# TinyFunctionGenerator.net
KiCad netlist of a schematic drawn in EAGLE
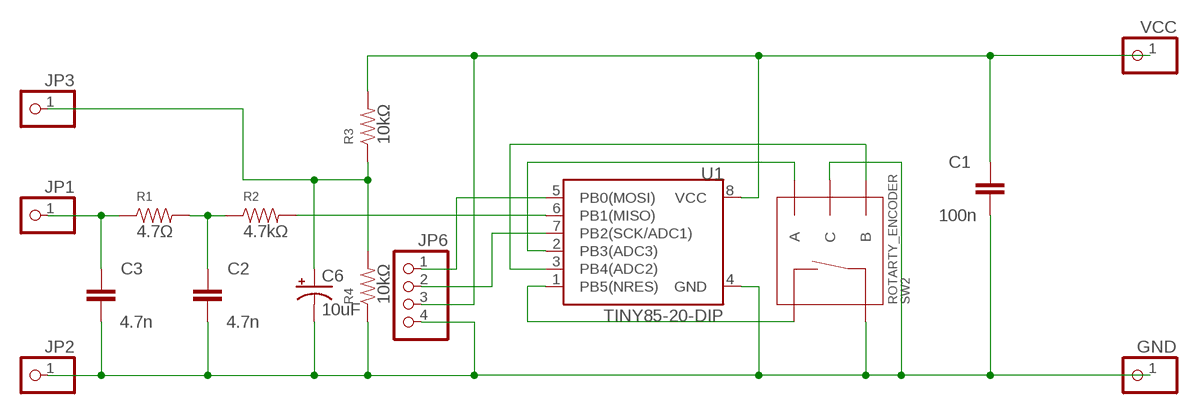
[diagram p0: schematic, sheet 1]

(export (version "E")
  (design (tool "Eeschema 10.0.6"))
  (components
    (comp (ref "C1")
      (value "100n")
      (footprint "eagle-import:AXIAL-5MM")
      (libsource (lib "eagle-import") (part "CAP_"))
    )
    (comp (ref "C2")
      (value "4.7n")
      (footprint "eagle-import:CAP-PTH-SMALL")
      (libsource (lib "eagle-import") (part "CAPPTH"))
    )
    (comp (ref "C3")
      (value "4.7n")
      (footprint "eagle-import:CAP-PTH-SMALL")
      (libsource (lib "eagle-import") (part "CAPPTH"))
    )
    (comp (ref "C6")
      (value "10uF")
      (footprint "eagle-import:CPOL-RADIAL-10UF-25V")
      (libsource (lib "eagle-import") (part "10UF-25V-20%(PTH)"))
    )
    (comp (ref "GND")
      (value "PINHD-1X1CB")
      (footprint "eagle-import:1X01-CLEANBIG")
      (libsource (lib "eagle-import") (part "PINHD-1X1CB"))
    )
    (comp (ref "JP1")
      (value "PINHD-1X1CB")
      (footprint "eagle-import:1X01-CLEANBIG")
      (libsource (lib "eagle-import") (part "PINHD-1X1CB"))
    )
    (comp (ref "JP2")
      (value "PINHD-1X1CB")
      (footprint "eagle-import:1X01-CLEANBIG")
      (libsource (lib "eagle-import") (part "PINHD-1X1CB"))
    )
    (comp (ref "JP3")
      (value "PINHD-1X1CB")
      (footprint "eagle-import:1X01-CLEANBIG")
      (libsource (lib "eagle-import") (part "PINHD-1X1CB"))
    )
    (comp (ref "JP6")
      (value "HEADER-1X4ROUND")
      (footprint "eagle-import:1X04_ROUND")
      (libsource (lib "eagle-import") (part "HEADER-1X4ROUND"))
    )
    (comp (ref "R1")
      (value "4.7Ω")
      (footprint "eagle-import:AXIAL-0.4")
      (libsource (lib "eagle-import") (part "RESISTORPTH-1/4W"))
    )
    (comp (ref "R2")
      (value "4.7kΩ")
      (footprint "eagle-import:AXIAL-0.4")
      (libsource (lib "eagle-import") (part "RESISTORPTH-1/4W"))
    )
    (comp (ref "R3")
      (value "10kΩ")
      (footprint "eagle-import:AXIAL-0.4")
      (libsource (lib "eagle-import") (part "RESISTORPTH-1/4W"))
    )
    (comp (ref "R4")
      (value "10kΩ")
      (footprint "eagle-import:AXIAL-0.4")
      (libsource (lib "eagle-import") (part "RESISTORPTH-1/4W"))
    )
    (comp (ref "SW2")
      (value "ROTARTY_ENCODER")
      (footprint "eagle-import:ROTARY_ENC_PLAIN")
      (libsource (lib "eagle-import") (part "ROTARTY_ENCODER"))
    )
    (comp (ref "U1")
      (value "TINY85-20-DIP")
      (footprint "eagle-import:DIP08")
      (libsource (lib "eagle-import") (part "ATTINY45TINY85-20-DIP"))
    )
    (comp (ref "VCC")
      (value "PINHD-1X1CB")
      (footprint "eagle-import:1X01-CLEANBIG")
      (libsource (lib "eagle-import") (part "PINHD-1X1CB"))
    )
  )
  (nets
    (net (code "1") (name "Net-(C1-1)") (class "Default")
      (node (ref "C1") (pin "P$1") (pinfunction "1_P$1") (pintype "passive"))
      (node (ref "JP6") (pin "3") (pinfunction "3_3") (pintype "passive"))
      (node (ref "R3") (pin "P$2") (pinfunction "2_P$2") (pintype "passive"))
      (node (ref "U1") (pin "8") (pinfunction "VCC_8") (pintype "bidirectional"))
      (node (ref "VCC") (pin "1") (pinfunction "1_1") (pintype "passive"))
    )
    (net (code "2") (name "Net-(C1-2)") (class "Default")
      (node (ref "C1") (pin "P$2") (pinfunction "2_P$2") (pintype "passive"))
      (node (ref "C2") (pin "2") (pinfunction "2_2") (pintype "passive"))
      (node (ref "C3") (pin "2") (pinfunction "2_2") (pintype "passive"))
      (node (ref "C6") (pin "2") (pinfunction "-_2") (pintype "passive"))
      (node (ref "GND") (pin "1") (pinfunction "1_1") (pintype "passive"))
      (node (ref "JP2") (pin "1") (pinfunction "1_1") (pintype "passive"))
      (node (ref "JP6") (pin "4") (pinfunction "4_4") (pintype "passive"))
      (node (ref "R4") (pin "P$1") (pinfunction "1_P$1") (pintype "passive"))
      (node (ref "SW2") (pin "C") (pinfunction "C_C") (pintype "bidirectional"))
      (node (ref "SW2") (pin "SW+") (pinfunction "SW+_SW+") (pintype "bidirectional"))
      (node (ref "U1") (pin "4") (pinfunction "GND_4") (pintype "bidirectional"))
    )
    (net (code "3") (name "Net-(C6-+)") (class "Default")
      (node (ref "C6") (pin "1") (pinfunction "+_1") (pintype "passive"))
      (node (ref "JP3") (pin "1") (pinfunction "1_1") (pintype "passive"))
      (node (ref "R3") (pin "P$1") (pinfunction "1_P$1") (pintype "passive"))
      (node (ref "R4") (pin "P$2") (pinfunction "2_P$2") (pintype "passive"))
    )
    (net (code "4") (name "Net-(R1-1)") (class "Default")
      (node (ref "C3") (pin "1") (pinfunction "1_1") (pintype "passive"))
      (node (ref "JP1") (pin "1") (pinfunction "1_1") (pintype "passive"))
      (node (ref "R1") (pin "P$1") (pinfunction "1_P$1") (pintype "passive"))
    )
    (net (code "5") (name "Net-(R1-2)") (class "Default")
      (node (ref "C2") (pin "1") (pinfunction "1_1") (pintype "passive"))
      (node (ref "R1") (pin "P$2") (pinfunction "2_P$2") (pintype "passive"))
      (node (ref "R2") (pin "P$1") (pinfunction "1_P$1") (pintype "passive"))
    )
    (net (code "6") (name "Net-(R2-2)") (class "Default")
      (node (ref "R2") (pin "P$2") (pinfunction "2_P$2") (pintype "passive"))
      (node (ref "U1") (pin "6") (pinfunction "PB1(MISO)_6") (pintype "bidirectional"))
    )
    (net (code "7") (name "Net-(U1-PB0(MOSI))") (class "Default")
      (node (ref "JP6") (pin "1") (pinfunction "1_1") (pintype "passive"))
      (node (ref "U1") (pin "5") (pinfunction "PB0(MOSI)_5") (pintype "bidirectional"))
    )
    (net (code "8") (name "Net-(U1-PB2(SCK{slash}ADC1))") (class "Default")
      (node (ref "JP6") (pin "2") (pinfunction "2_2") (pintype "passive"))
      (node (ref "U1") (pin "7") (pinfunction "PB2(SCK/ADC1)_7") (pintype "bidirectional"))
    )
    (net (code "9") (name "Net-(U1-PB3(ADC3))") (class "Default")
      (node (ref "SW2") (pin "A") (pinfunction "A_A") (pintype "bidirectional"))
      (node (ref "U1") (pin "2") (pinfunction "PB3(ADC3)_2") (pintype "bidirectional"))
    )
    (net (code "10") (name "Net-(U1-PB4(ADC2))") (class "Default")
      (node (ref "SW2") (pin "B") (pinfunction "B_B") (pintype "bidirectional"))
      (node (ref "U1") (pin "3") (pinfunction "PB4(ADC2)_3") (pintype "bidirectional"))
    )
    (net (code "11") (name "Net-(U1-PB5(NRES))") (class "Default")
      (node (ref "SW2") (pin "SW-") (pinfunction "SW-_SW-") (pintype "bidirectional"))
      (node (ref "U1") (pin "1") (pinfunction "PB5(NRES)_1") (pintype "bidirectional"))
    )
  )
)
